# GR_Split.net
KiCad netlist of a schematic drawn in Altium Designer
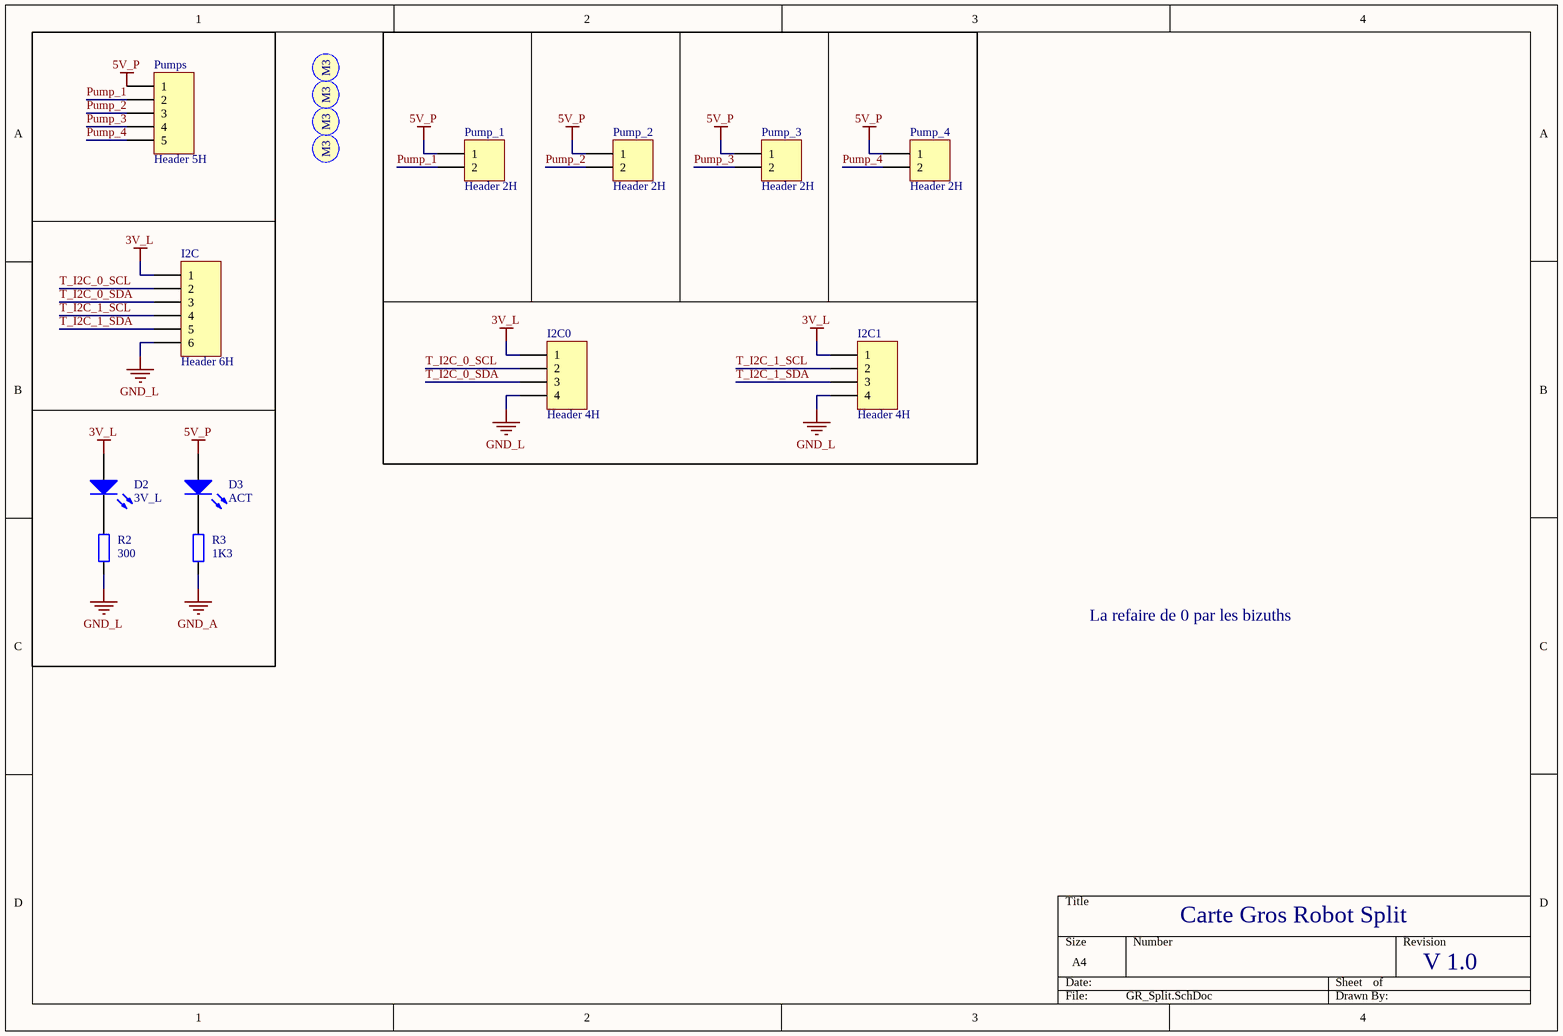
[diagram p0: GR_Split.SchDoc]

(export (version "E")
  (design (tool "Eeschema 10.0.6"))
  (components
    (comp (ref "D2")
      (value "3V_L")
      (footprint "KP-3216SEC")
      (description "Typical RED, GREEN, YELLOW, AMBER GaAs LED")
      (fields (field (name "PUBLISHER") "Altium Limited"))
      (libsource (lib "Miscellaneous Devices") (part "LED2"))
    )
    (comp (ref "D3")
      (value "ACT")
      (footprint "KP-3216SEC")
      (description "Typical RED, GREEN, YELLOW, AMBER GaAs LED")
      (fields (field (name "PUBLISHER") "Altium Limited"))
      (libsource (lib "Miscellaneous Devices") (part "LED2"))
    )
    (comp (ref "I2C")
      (value "Header 6H")
      (footprint "B6B-XH-A")
      (description "Header, 6-Pin, Right Angle")
      (fields (field (name "PUBLISHER") "Altium Limited"))
      (libsource (lib "Miscellaneous Connectors") (part "Header 6H"))
    )
    (comp (ref "I2C0")
      (value "Header 4H")
      (footprint "B4B-XH-A")
      (description "Header, 4-Pin, Right Angle")
      (fields (field (name "PUBLISHER") "Altium Limited"))
      (libsource (lib "Miscellaneous Connectors") (part "Header 4H"))
    )
    (comp (ref "I2C1")
      (value "Header 4H")
      (footprint "B4B-XH-A")
      (description "Header, 4-Pin, Right Angle")
      (fields (field (name "PUBLISHER") "Altium Limited"))
      (libsource (lib "Miscellaneous Connectors") (part "Header 4H"))
    )
    (comp (ref "Pumps")
      (value "Header 5H")
      (footprint "HDR1X5H")
      (description "Header, 5-Pin, Right Angle")
      (fields (field (name "PUBLISHER") "Altium Limited"))
      (libsource (lib "Miscellaneous Connectors") (part "Header 5H"))
    )
    (comp (ref "Pump_1")
      (value "Header 2H")
      (footprint "S2B-XH-A")
      (description "Header, 2-Pin, Right Angle")
      (fields (field (name "PUBLISHER") "Altium Limited"))
      (libsource (lib "Miscellaneous Connectors") (part "Header 2H"))
    )
    (comp (ref "Pump_2")
      (value "Header 2H")
      (footprint "S2B-XH-A")
      (description "Header, 2-Pin, Right Angle")
      (fields (field (name "PUBLISHER") "Altium Limited"))
      (libsource (lib "Miscellaneous Connectors") (part "Header 2H"))
    )
    (comp (ref "Pump_3")
      (value "Header 2H")
      (footprint "S2B-XH-A")
      (description "Header, 2-Pin, Right Angle")
      (fields (field (name "PUBLISHER") "Altium Limited"))
      (libsource (lib "Miscellaneous Connectors") (part "Header 2H"))
    )
    (comp (ref "Pump_4")
      (value "Header 2H")
      (footprint "S2B-XH-A")
      (description "Header, 2-Pin, Right Angle")
      (fields (field (name "PUBLISHER") "Altium Limited"))
      (libsource (lib "Miscellaneous Connectors") (part "Header 2H"))
    )
    (comp (ref "R2")
      (value "300")
      (footprint "Resistor 1206")
      (description "Resistor")
      (fields (field (name "Comment") "Res2") (field (name "PUBLISHER") "Altium Limited"))
      (libsource (lib "Miscellaneous Devices") (part "Res2"))
    )
    (comp (ref "R3")
      (value "1K3")
      (footprint "Resistor 1206")
      (description "Resistor")
      (fields (field (name "Comment") "Res2") (field (name "PUBLISHER") "Altium Limited"))
      (libsource (lib "") (part "Res2_1"))
    )
    (comp (ref "S1")
      (value "Screw M3")
      (footprint "Screw M3")
      (libsource (lib "SupaeroRobot") (part "Screw M3"))
    )
    (comp (ref "S2")
      (value "Screw M3")
      (footprint "Screw M3")
      (libsource (lib "SupaeroRobot") (part "Screw M3"))
    )
    (comp (ref "S3")
      (value "Screw M3")
      (footprint "Screw M3")
      (libsource (lib "SupaeroRobot") (part "Screw M3"))
    )
    (comp (ref "S4")
      (value "Screw M3")
      (footprint "Screw M3")
      (libsource (lib "SupaeroRobot") (part "Screw M3"))
    )
  )
  (nets
    (net (code "1") (name "/Pump_1") (class "Default")
      (node (ref "Pump_1") (pin "2") (pinfunction "2_2") (pintype "passive"))
      (node (ref "Pumps") (pin "2") (pinfunction "2_2") (pintype "passive"))
    )
    (net (code "2") (name "/Pump_2") (class "Default")
      (node (ref "Pump_2") (pin "2") (pinfunction "2_2") (pintype "passive"))
      (node (ref "Pumps") (pin "3") (pinfunction "3_3") (pintype "passive"))
    )
    (net (code "3") (name "/Pump_3") (class "Default")
      (node (ref "Pump_3") (pin "2") (pinfunction "2_2") (pintype "passive"))
      (node (ref "Pumps") (pin "4") (pinfunction "4_4") (pintype "passive"))
    )
    (net (code "4") (name "/Pump_4") (class "Default")
      (node (ref "Pump_4") (pin "2") (pinfunction "2_2") (pintype "passive"))
      (node (ref "Pumps") (pin "5") (pinfunction "5_5") (pintype "passive"))
    )
    (net (code "5") (name "/T_I2C_0_SCL") (class "Default")
      (node (ref "I2C") (pin "2") (pinfunction "2_2") (pintype "passive"))
      (node (ref "I2C0") (pin "2") (pinfunction "2_2") (pintype "passive"))
    )
    (net (code "6") (name "/T_I2C_0_SDA") (class "Default")
      (node (ref "I2C") (pin "3") (pinfunction "3_3") (pintype "passive"))
      (node (ref "I2C0") (pin "3") (pinfunction "3_3") (pintype "passive"))
    )
    (net (code "7") (name "/T_I2C_1_SCL") (class "Default")
      (node (ref "I2C") (pin "4") (pinfunction "4_4") (pintype "passive"))
      (node (ref "I2C1") (pin "2") (pinfunction "2_2") (pintype "passive"))
    )
    (net (code "8") (name "/T_I2C_1_SDA") (class "Default")
      (node (ref "I2C") (pin "5") (pinfunction "5_5") (pintype "passive"))
      (node (ref "I2C1") (pin "3") (pinfunction "3_3") (pintype "passive"))
    )
    (net (code "9") (name "3V_L") (class "Default")
      (node (ref "D2") (pin "1") (pinfunction "A_1") (pintype "passive"))
      (node (ref "I2C") (pin "1") (pinfunction "1_1") (pintype "passive"))
      (node (ref "I2C0") (pin "1") (pinfunction "1_1") (pintype "passive"))
      (node (ref "I2C1") (pin "1") (pinfunction "1_1") (pintype "passive"))
    )
    (net (code "10") (name "5V_P") (class "Default")
      (node (ref "D3") (pin "1") (pinfunction "A_1") (pintype "passive"))
      (node (ref "Pump_1") (pin "1") (pinfunction "1_1") (pintype "passive"))
      (node (ref "Pump_2") (pin "1") (pinfunction "1_1") (pintype "passive"))
      (node (ref "Pump_3") (pin "1") (pinfunction "1_1") (pintype "passive"))
      (node (ref "Pump_4") (pin "1") (pinfunction "1_1") (pintype "passive"))
      (node (ref "Pumps") (pin "1") (pinfunction "1_1") (pintype "passive"))
    )
    (net (code "11") (name "GND_A") (class "Default")
      (node (ref "R3") (pin "2") (pinfunction "2_2") (pintype "passive"))
    )
    (net (code "12") (name "GND_L") (class "Default")
      (node (ref "I2C") (pin "6") (pinfunction "6_6") (pintype "passive"))
      (node (ref "I2C0") (pin "4") (pinfunction "4_4") (pintype "passive"))
      (node (ref "I2C1") (pin "4") (pinfunction "4_4") (pintype "passive"))
      (node (ref "R2") (pin "1") (pinfunction "1_1") (pintype "passive"))
    )
    (net (code "13") (name "Net-(D2-K)") (class "Default")
      (node (ref "D2") (pin "2") (pinfunction "K_2") (pintype "passive"))
      (node (ref "R2") (pin "2") (pinfunction "2_2") (pintype "passive"))
    )
    (net (code "14") (name "Net-(D3-K)") (class "Default")
      (node (ref "D3") (pin "2") (pinfunction "K_2") (pintype "passive"))
      (node (ref "R3") (pin "1") (pinfunction "1_1") (pintype "passive"))
    )
  )
)
